# Standing_Desk_Controller_Schematic_v20_v.net
KiCad netlist of a schematic drawn in EAGLE
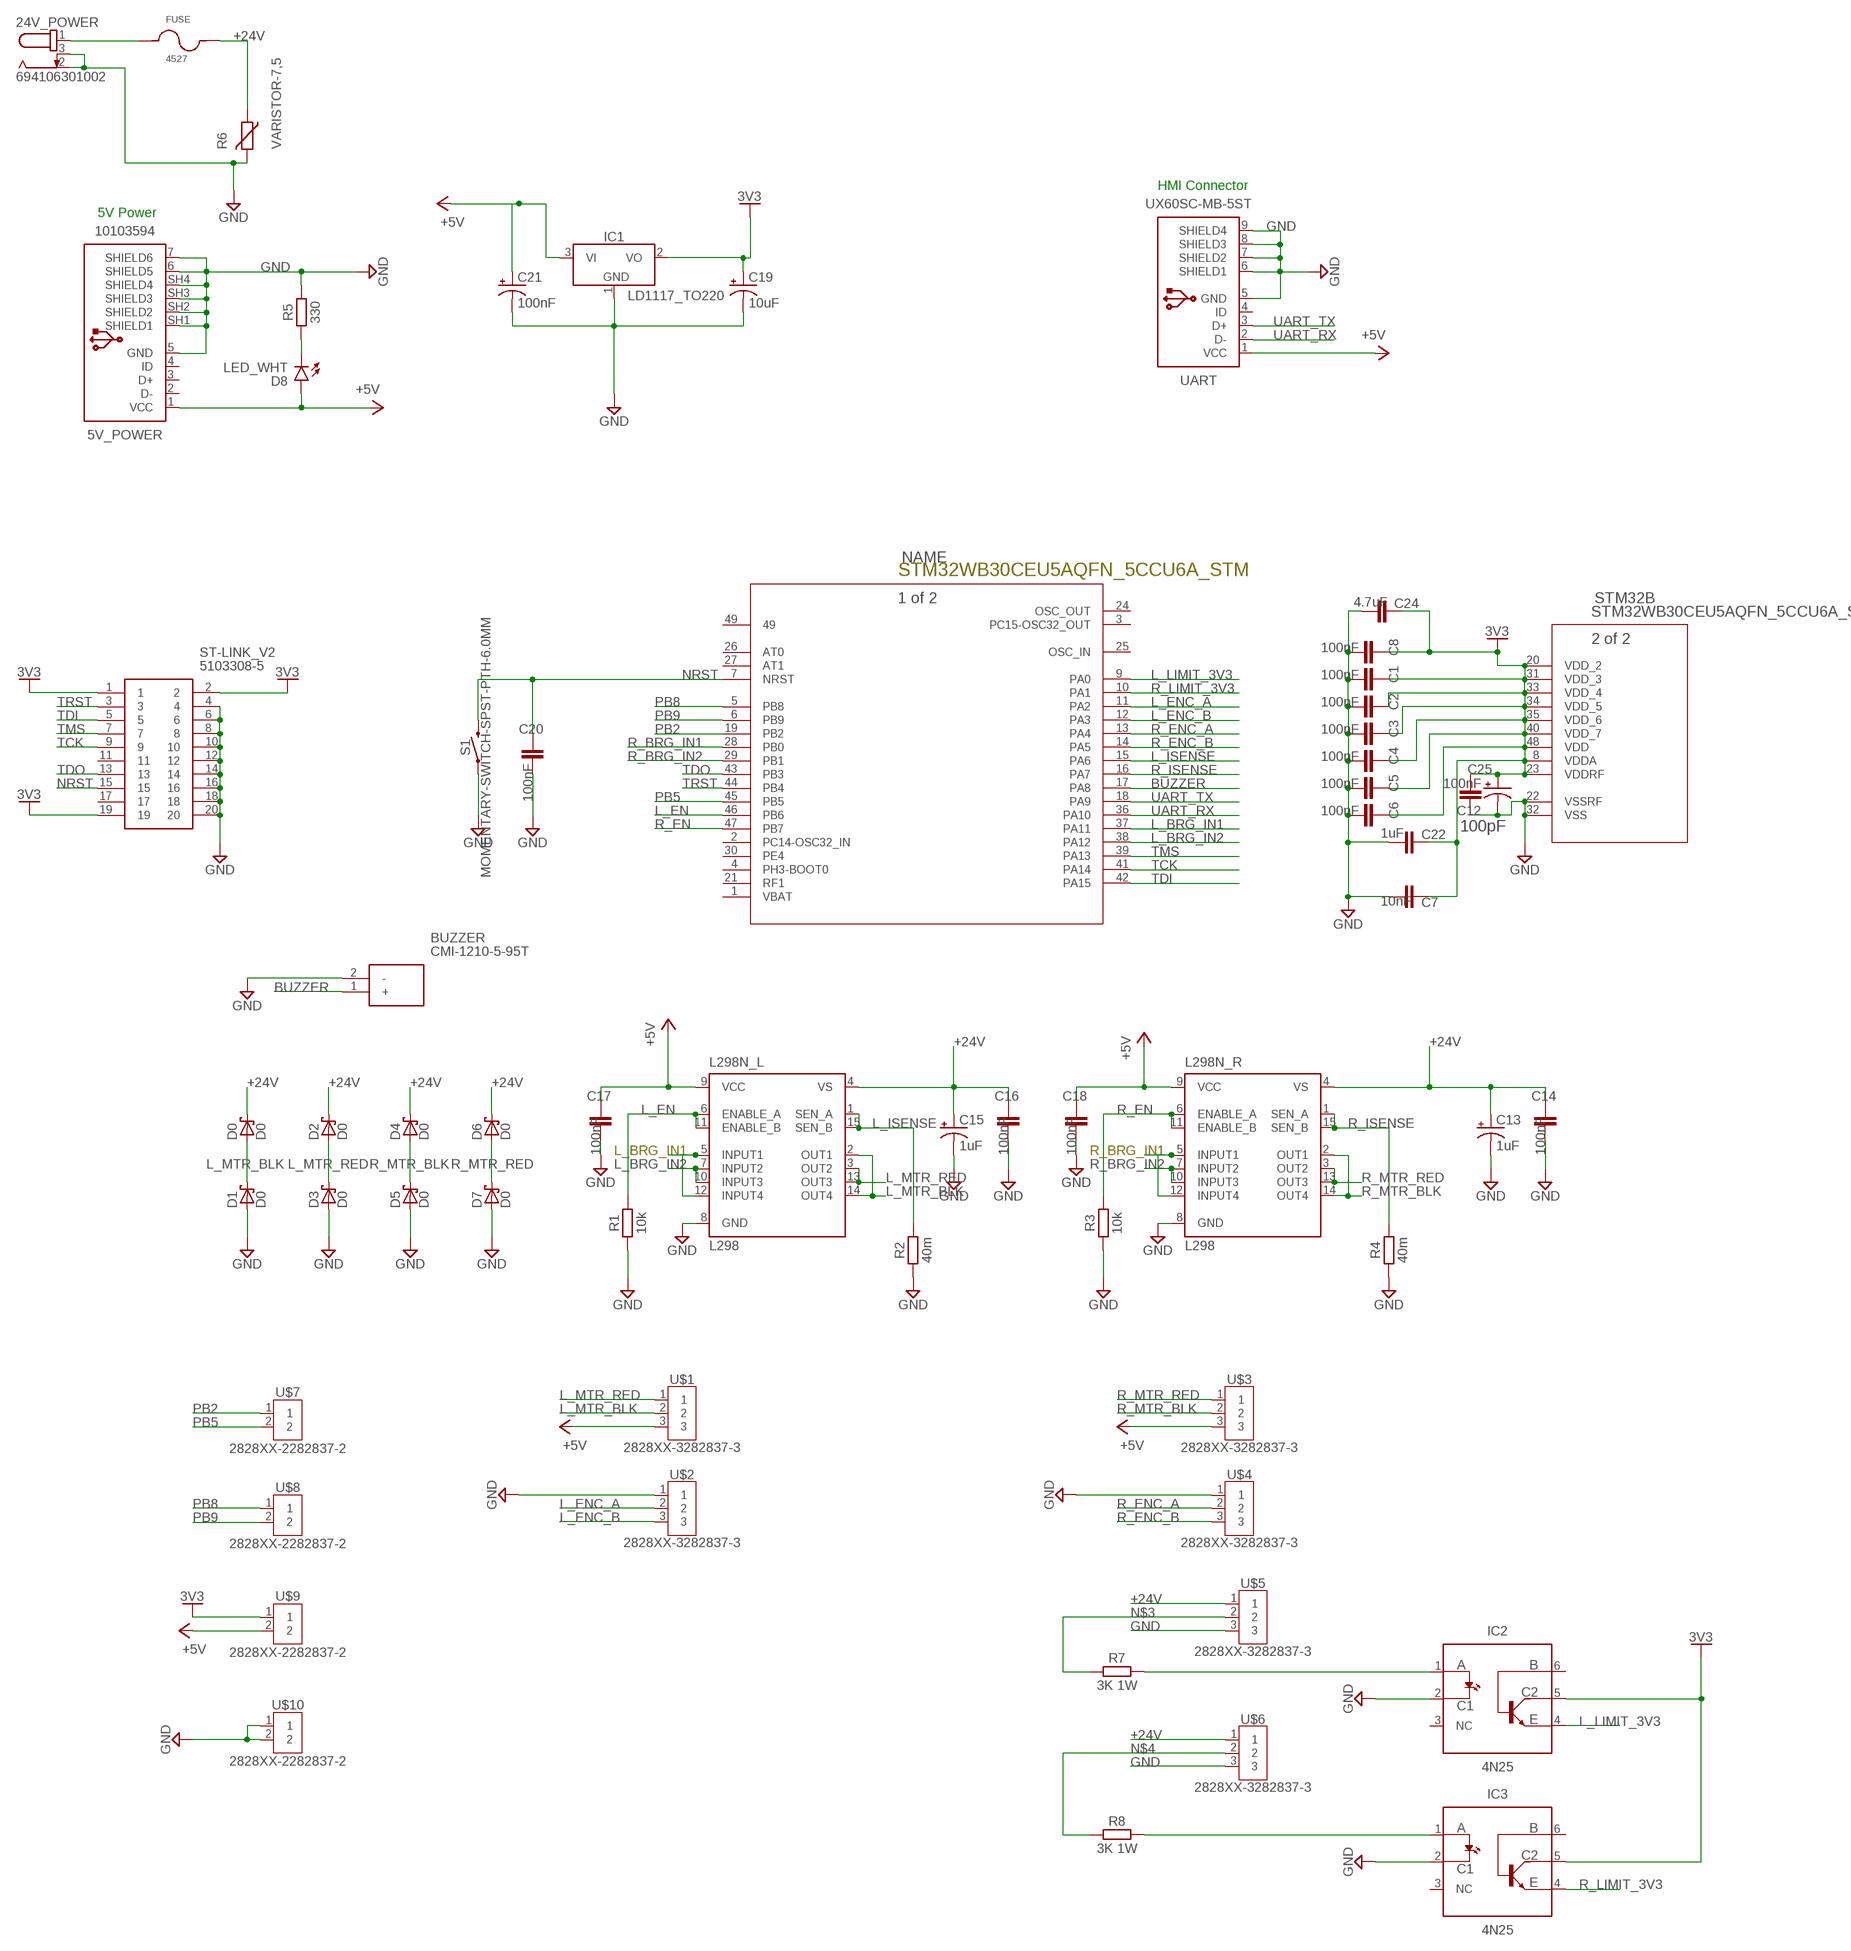
[diagram p0: schematic, sheet 1]

(export (version "E")
  (design (tool "Eeschema 10.0.6"))
  (components
    (comp (ref "5V_POWER")
      (value "10103594")
      (footprint "eagle-import:10103594")
      (fields (field (name "MANUFACTURER") "Amphenol ICC (FCI)") (field (name "MPN") "10103594-0001LF"))
      (libsource (lib "eagle-import") (part "10103594"))
    )
    (comp (ref "24V_POWER")
      (value "694106301002")
      (footprint "eagle-import:694106301002")
      (fields
        (field (name "DIGIKEY_PART_NUMBER") "732-5930-ND")
        (field (name "MANUFACTURER") "Wurth Electronics Inc.")
        (field (name "CREATED_BY") "PCBLayout.com")
      )
      (libsource (lib "eagle-import") (part "694106301002"))
    )
    (comp (ref "BUZZER")
      (value "CMI-1210-5-95T")
      (footprint "eagle-import:CMI1210595T")
      (fields (field (name "MOUSER_PART_NUMBER") "179-CMI-1210-5-95T"))
      (libsource (lib "eagle-import") (part "CMI-1210-5-95T"))
    )
    (comp (ref "C1")
      (value "100nF")
      (footprint "eagle-import:CAPC3216X135")
      (libsource (lib "eagle-import") (part "Capacitor_Bottom_Side_vf.a7xvLcyfRC6FgNyyCREhQg_CCHIP-1206(3216-METRIC)_"))
    )
    (comp (ref "C2")
      (value "100nF")
      (footprint "eagle-import:CAPC3216X135")
      (libsource (lib "eagle-import") (part "Capacitor_Bottom_Side_vf.a7xvLcyfRC6FgNyyCREhQg_CCHIP-1206(3216-METRIC)_"))
    )
    (comp (ref "C3")
      (value "100nF")
      (footprint "eagle-import:CAPC3216X135")
      (libsource (lib "eagle-import") (part "Capacitor_Bottom_Side_vf.a7xvLcyfRC6FgNyyCREhQg_CCHIP-1206(3216-METRIC)_"))
    )
    (comp (ref "C4")
      (value "100nF")
      (footprint "eagle-import:CAPC3216X135")
      (libsource (lib "eagle-import") (part "Capacitor_Bottom_Side_vf.a7xvLcyfRC6FgNyyCREhQg_CCHIP-1206(3216-METRIC)_"))
    )
    (comp (ref "C5")
      (value "100nF")
      (footprint "eagle-import:CAPC3216X135")
      (libsource (lib "eagle-import") (part "Capacitor_Bottom_Side_vf.a7xvLcyfRC6FgNyyCREhQg_CCHIP-1206(3216-METRIC)_"))
    )
    (comp (ref "C6")
      (value "100nF")
      (footprint "eagle-import:CAPC3216X135")
      (libsource (lib "eagle-import") (part "Capacitor_Bottom_Side_vf.a7xvLcyfRC6FgNyyCREhQg_CCHIP-1206(3216-METRIC)_"))
    )
    (comp (ref "C7")
      (value "10nF")
      (footprint "eagle-import:CAPRD550W60D1025H1250B")
      (libsource (lib "eagle-import") (part "CRADIAL-12.5MM-DIA_"))
    )
    (comp (ref "C8")
      (value "100nF")
      (footprint "eagle-import:CAPC3216X135")
      (libsource (lib "eagle-import") (part "Capacitor_Bottom_Side_vf.a7xvLcyfRC6FgNyyCREhQg_CCHIP-1206(3216-METRIC)_"))
    )
    (comp (ref "C12")
      (value "100nF")
      (footprint "eagle-import:CAPC3216X135")
      (libsource (lib "eagle-import") (part "Capacitor_Bottom_Side_vf.a7xvLcyfRC6FgNyyCREhQg_CCHIP-1206(3216-METRIC)_"))
    )
    (comp (ref "C13")
      (value "1uF")
      (footprint "eagle-import:E2,5-6")
      (libsource (lib "eagle-import") (part "CPOL-USE2.5-6"))
    )
    (comp (ref "C14")
      (value "100nF")
      (footprint "eagle-import:CAPC3216X135")
      (libsource (lib "eagle-import") (part "Capacitor_16290819_CCHIP-1206(3216-METRIC)_"))
    )
    (comp (ref "C15")
      (value "1uF")
      (footprint "eagle-import:E2,5-6")
      (libsource (lib "eagle-import") (part "CPOL-USE2.5-6"))
    )
    (comp (ref "C16")
      (value "100nF")
      (footprint "eagle-import:CAPC3216X135")
      (libsource (lib "eagle-import") (part "Capacitor_16290819_CCHIP-1206(3216-METRIC)_"))
    )
    (comp (ref "C17")
      (value "100nF")
      (footprint "eagle-import:CAPC3216X135")
      (libsource (lib "eagle-import") (part "Capacitor_16290819_CCHIP-1206(3216-METRIC)_"))
    )
    (comp (ref "C18")
      (value "100nF")
      (footprint "eagle-import:CAPC3216X135")
      (libsource (lib "eagle-import") (part "Capacitor_16290819_CCHIP-1206(3216-METRIC)_"))
    )
    (comp (ref "C19")
      (value "10uF")
      (footprint "eagle-import:E2,5-6")
      (libsource (lib "eagle-import") (part "CPOL-USE2.5-6"))
    )
    (comp (ref "C20")
      (value "100nF")
      (footprint "eagle-import:CAPC3216X135")
      (libsource (lib "eagle-import") (part "Capacitor_16290819_CCHIP-1206(3216-METRIC)_"))
    )
    (comp (ref "C21")
      (value "100nF")
      (footprint "eagle-import:E2,5-6")
      (libsource (lib "eagle-import") (part "CPOL-USE2.5-6"))
    )
    (comp (ref "C22")
      (value "1uF")
      (footprint "eagle-import:CAPRD550W60D1025H1250B")
      (libsource (lib "eagle-import") (part "CRADIAL-12.5MM-DIA_"))
    )
    (comp (ref "C24")
      (value "4.7uF")
      (footprint "eagle-import:CAPRD550W60D1025H1250B")
      (libsource (lib "eagle-import") (part "CRADIAL-12.5MM-DIA_"))
    )
    (comp (ref "C25")
      (value "100pF")
      (footprint "eagle-import:E2,5-6")
      (libsource (lib "eagle-import") (part "CPOL-USE2.5-6"))
    )
    (comp (ref "D0")
      (value "D0")
      (footprint "eagle-import:SOD106A-W")
      (libsource (lib "eagle-import") (part "SS14CT-ND"))
    )
    (comp (ref "D1")
      (value "D0")
      (footprint "eagle-import:SOD106A-W")
      (libsource (lib "eagle-import") (part "SS14CT-ND"))
    )
    (comp (ref "D2")
      (value "D0")
      (footprint "eagle-import:SOD106A-W")
      (libsource (lib "eagle-import") (part "SS14CT-ND"))
    )
    (comp (ref "D3")
      (value "D0")
      (footprint "eagle-import:SOD106A-W")
      (libsource (lib "eagle-import") (part "SS14CT-ND"))
    )
    (comp (ref "D4")
      (value "D0")
      (footprint "eagle-import:SOD106A-W")
      (libsource (lib "eagle-import") (part "SS14CT-ND"))
    )
    (comp (ref "D5")
      (value "D0")
      (footprint "eagle-import:SOD106A-W")
      (libsource (lib "eagle-import") (part "SS14CT-ND"))
    )
    (comp (ref "D6")
      (value "D0")
      (footprint "eagle-import:SOD106A-W")
      (libsource (lib "eagle-import") (part "SS14CT-ND"))
    )
    (comp (ref "D7")
      (value "D0")
      (footprint "eagle-import:SOD106A-W")
      (libsource (lib "eagle-import") (part "SS14CT-ND"))
    )
    (comp (ref "D8")
      (value "LED_WHT")
      (footprint "eagle-import:LEDC3216X75N_FLAT-B")
      (libsource (lib "eagle-import") (part "CHIP-FLAT-B_1206"))
    )
    (comp (ref "FUSE")
      (value "4527")
      (footprint "eagle-import:4527")
      (fields
        (field (name "MANUFACTURER") "Keystone Electronics")
        (field (name "CREATED_BY") "PCBLayout.com")
      )
      (libsource (lib "eagle-import") (part "4527"))
    )
    (comp (ref "IC1")
      (value "LD1117_TO220")
      (footprint "eagle-import:TO220V")
      (fields (field (name "MANUFACTURER") "STMicroelectronics") (field (name "MPN") "Generic"))
      (libsource (lib "eagle-import") (part "LD1117_TO220"))
    )
    (comp (ref "IC2")
      (value "4N25")
      (footprint "eagle-import:DIP762W60P254L712H480Q6B")
      (fields (field (name "MANUFACTURER") "Vishay"))
      (libsource (lib "eagle-import") (part "4N25"))
    )
    (comp (ref "IC3")
      (value "4N25")
      (footprint "eagle-import:DIP762W60P254L712H480Q6B")
      (fields (field (name "MANUFACTURER") "Vishay"))
      (libsource (lib "eagle-import") (part "4N25"))
    )
    (comp (ref "L298N_L")
      (value "L298")
      (footprint "eagle-import:MULTIWATT-15")
      (fields (field (name "MPN") "L298N"))
      (libsource (lib "eagle-import") (part "L298"))
    )
    (comp (ref "L298N_R")
      (value "L298")
      (footprint "eagle-import:MULTIWATT-15")
      (fields (field (name "MPN") "L298N"))
      (libsource (lib "eagle-import") (part "L298"))
    )
    (comp (ref "R1")
      (value "10k")
      (footprint "eagle-import:RESC3216X70")
      (libsource (lib "eagle-import") (part "RCHIP-1206(3216-METRIC)_"))
    )
    (comp (ref "R2")
      (value "40m")
      (footprint "eagle-import:RESC3216X70")
      (libsource (lib "eagle-import") (part "RCHIP-1206(3216-METRIC)_"))
    )
    (comp (ref "R3")
      (value "10k")
      (footprint "eagle-import:RESC3216X70")
      (libsource (lib "eagle-import") (part "RCHIP-1206(3216-METRIC)_"))
    )
    (comp (ref "R4")
      (value "40m")
      (footprint "eagle-import:RESC3216X70")
      (libsource (lib "eagle-import") (part "RCHIP-1206(3216-METRIC)_"))
    )
    (comp (ref "R5")
      (value "330")
      (footprint "eagle-import:RESC3216X70")
      (libsource (lib "eagle-import") (part "RCHIP-1206(3216-METRIC)_"))
    )
    (comp (ref "R6")
      (value "VARISTOR-7,5")
      (footprint "eagle-import:R-7,5")
      (libsource (lib "eagle-import") (part "VARISTOR-7,5"))
    )
    (comp (ref "R7")
      (value "3K 1W")
      (footprint "eagle-import:RESAD724W46L381D178B")
      (libsource (lib "eagle-import") (part "RAXIAL-7.2MM-PITCH_"))
    )
    (comp (ref "R8")
      (value "3K 1W")
      (footprint "eagle-import:RESAD724W46L381D178B")
      (libsource (lib "eagle-import") (part "RAXIAL-7.2MM-PITCH_"))
    )
    (comp (ref "S1")
      (value "MOMENTARY-SWITCH-SPST-PTH-6.0MM")
      (footprint "eagle-import:TACTILE_SWITCH_PTH_6.0MM")
      (libsource (lib "eagle-import") (part "MOMENTARY-SWITCH-SPST-PTH-6.0MM"))
    )
    (comp (ref "ST-LINK_V2")
      (value "5103308-5")
      (footprint "eagle-import:SHDR20W66P254_2X10_3289X914X98")
      (fields (field (name "MOUSER_PART_NUMBER") "571-5103308-5"))
      (libsource (lib "eagle-import") (part "5103308-5"))
    )
    (comp (ref "STM32")
      (value "STM32WB30CEU5AQFN_5CCU6A_STM")
      (footprint "eagle-import:QFN_5CCU6A_STM")
      (fields
        (field (name "MANUFACTURER_PART_NUMBER") "STM32WB30CEU5A")
        (field (name "COPYRIGHT") "Copyright (C) 2022 Ultra Librarian. All rights reserved.")
      )
      (libsource (lib "eagle-import") (part "STM32WB30CEU5AQFN_5CCU6A_STM"))
    )
    (comp (ref "U$1")
      (value "2828XX-3282837-3")
      (footprint "eagle-import:TERMBLK_508-3N")
      (fields (field (name "MANUFACTURER") "TE Connectivity") (field (name "MPN") "282837-3"))
      (libsource (lib "eagle-import") (part "2828XX-3282837-3"))
    )
    (comp (ref "U$2")
      (value "2828XX-3282837-3")
      (footprint "eagle-import:TERMBLK_508-3N")
      (fields (field (name "MANUFACTURER") "TE Connectivity") (field (name "MPN") "282837-3"))
      (libsource (lib "eagle-import") (part "2828XX-3282837-3"))
    )
    (comp (ref "U$3")
      (value "2828XX-3282837-3")
      (footprint "eagle-import:TERMBLK_508-3N")
      (fields (field (name "MANUFACTURER") "TE Connectivity") (field (name "MPN") "282837-3"))
      (libsource (lib "eagle-import") (part "2828XX-3282837-3"))
    )
    (comp (ref "U$4")
      (value "2828XX-3282837-3")
      (footprint "eagle-import:TERMBLK_508-3N")
      (fields (field (name "MANUFACTURER") "TE Connectivity") (field (name "MPN") "282837-3"))
      (libsource (lib "eagle-import") (part "2828XX-3282837-3"))
    )
    (comp (ref "U$5")
      (value "2828XX-3282837-3")
      (footprint "eagle-import:TERMBLK_508-3N")
      (fields (field (name "MANUFACTURER") "TE Connectivity") (field (name "MPN") "282837-3"))
      (libsource (lib "eagle-import") (part "2828XX-3282837-3"))
    )
    (comp (ref "U$6")
      (value "2828XX-3282837-3")
      (footprint "eagle-import:TERMBLK_508-3N")
      (fields (field (name "MANUFACTURER") "TE Connectivity") (field (name "MPN") "282837-3"))
      (libsource (lib "eagle-import") (part "2828XX-3282837-3"))
    )
    (comp (ref "U$7")
      (value "2828XX-2282837-2")
      (footprint "eagle-import:TERMBLK_508-2N")
      (fields (field (name "MANUFACTURER") "TE Connectivity") (field (name "MPN") "282837-2"))
      (libsource (lib "eagle-import") (part "2828XX-2282837-2"))
    )
    (comp (ref "U$8")
      (value "2828XX-2282837-2")
      (footprint "eagle-import:TERMBLK_508-2N")
      (fields (field (name "MANUFACTURER") "TE Connectivity") (field (name "MPN") "282837-2"))
      (libsource (lib "eagle-import") (part "2828XX-2282837-2"))
    )
    (comp (ref "U$9")
      (value "2828XX-2282837-2")
      (footprint "eagle-import:TERMBLK_508-2N")
      (fields (field (name "MANUFACTURER") "TE Connectivity") (field (name "MPN") "282837-2"))
      (libsource (lib "eagle-import") (part "2828XX-2282837-2"))
    )
    (comp (ref "U$10")
      (value "2828XX-2282837-2")
      (footprint "eagle-import:TERMBLK_508-2N")
      (fields (field (name "MANUFACTURER") "TE Connectivity") (field (name "MPN") "282837-2"))
      (libsource (lib "eagle-import") (part "2828XX-2282837-2"))
    )
    (comp (ref "UART")
      (value "UX60SC-MB-5ST")
      (footprint "eagle-import:UX60SC-MB-5ST")
      (fields
        (field (name "MANUFACTURER") "Hirose Electric Co. Ltd")
        (field (name "MPN") "UX60SC-MB-5ST(80)")
      )
      (libsource (lib "eagle-import") (part "UX60SC-MB-5ST"))
    )
  )
  (nets
    (net (code "1") (name "+5V") (class "Default")
      (node (ref "5V_POWER") (pin "1") (pinfunction "VCC_1") (pintype "power_in"))
      (node (ref "C17") (pin "1") (pinfunction "1_1") (pintype "passive"))
      (node (ref "C18") (pin "1") (pinfunction "1_1") (pintype "passive"))
      (node (ref "C21") (pin "+") (pinfunction "+_+") (pintype "passive"))
      (node (ref "D8") (pin "A") (pinfunction "A_A") (pintype "passive"))
      (node (ref "IC1") (pin "3") (pinfunction "VI_3") (pintype "input"))
      (node (ref "L298N_L") (pin "9") (pinfunction "VCC_9") (pintype "power_in"))
      (node (ref "L298N_R") (pin "9") (pinfunction "VCC_9") (pintype "power_in"))
      (node (ref "U$1") (pin "3") (pinfunction "3_3") (pintype "bidirectional"))
      (node (ref "U$3") (pin "3") (pinfunction "3_3") (pintype "bidirectional"))
      (node (ref "U$9") (pin "2") (pinfunction "2_2") (pintype "bidirectional"))
      (node (ref "UART") (pin "1") (pinfunction "VCC_1") (pintype "power_in"))
    )
    (net (code "2") (name "/+24V") (class "Default")
      (node (ref "C13") (pin "+") (pinfunction "+_+") (pintype "passive"))
      (node (ref "C14") (pin "1") (pinfunction "1_1") (pintype "passive"))
      (node (ref "C15") (pin "+") (pinfunction "+_+") (pintype "passive"))
      (node (ref "C16") (pin "1") (pinfunction "1_1") (pintype "passive"))
      (node (ref "D0") (pin "C") (pinfunction "C_C") (pintype "passive"))
      (node (ref "D2") (pin "C") (pinfunction "C_C") (pintype "passive"))
      (node (ref "D4") (pin "C") (pinfunction "C_C") (pintype "passive"))
      (node (ref "D6") (pin "C") (pinfunction "C_C") (pintype "passive"))
      (node (ref "FUSE") (pin "2") (pinfunction "2_2") (pintype "passive"))
      (node (ref "L298N_L") (pin "4") (pinfunction "VS_4") (pintype "power_in"))
      (node (ref "L298N_R") (pin "4") (pinfunction "VS_4") (pintype "power_in"))
      (node (ref "R6") (pin "1") (pinfunction "1_1") (pintype "passive"))
      (node (ref "U$5") (pin "1") (pinfunction "1_1") (pintype "bidirectional"))
      (node (ref "U$6") (pin "1") (pinfunction "1_1") (pintype "bidirectional"))
    )
    (net (code "3") (name "/BUZZER") (class "Default")
      (node (ref "BUZZER") (pin "1") (pinfunction "+_1") (pintype "bidirectional"))
      (node (ref "STM32") (pin "17") (pinfunction "PA8_17") (pintype "bidirectional"))
    )
    (net (code "4") (name "/L_BRG_IN1") (class "Default")
      (node (ref "L298N_L") (pin "12") (pinfunction "INPUT4_12") (pintype "input"))
      (node (ref "L298N_L") (pin "5") (pinfunction "INPUT1_5") (pintype "input"))
      (node (ref "STM32") (pin "37") (pinfunction "PA11_37") (pintype "bidirectional"))
    )
    (net (code "5") (name "/L_BRG_IN2") (class "Default")
      (node (ref "L298N_L") (pin "10") (pinfunction "INPUT3_10") (pintype "input"))
      (node (ref "L298N_L") (pin "7") (pinfunction "INPUT2_7") (pintype "input"))
      (node (ref "STM32") (pin "38") (pinfunction "PA12_38") (pintype "bidirectional"))
    )
    (net (code "6") (name "/L_EN") (class "Default")
      (node (ref "L298N_L") (pin "11") (pinfunction "ENABLE_B_11") (pintype "input"))
      (node (ref "L298N_L") (pin "6") (pinfunction "ENABLE_A_6") (pintype "input"))
      (node (ref "R1") (pin "2") (pinfunction "2_2") (pintype "passive"))
      (node (ref "STM32") (pin "46") (pinfunction "PB6_46") (pintype "bidirectional"))
    )
    (net (code "7") (name "/L_ENC_A") (class "Default")
      (node (ref "STM32") (pin "11") (pinfunction "PA2_11") (pintype "bidirectional"))
      (node (ref "U$2") (pin "2") (pinfunction "2_2") (pintype "bidirectional"))
    )
    (net (code "8") (name "/L_ENC_B") (class "Default")
      (node (ref "STM32") (pin "12") (pinfunction "PA3_12") (pintype "bidirectional"))
      (node (ref "U$2") (pin "3") (pinfunction "3_3") (pintype "bidirectional"))
    )
    (net (code "9") (name "/L_ISENSE") (class "Default")
      (node (ref "L298N_L") (pin "1") (pinfunction "SEN_A_1") (pintype "input"))
      (node (ref "L298N_L") (pin "15") (pinfunction "SEN_B_15") (pintype "input"))
      (node (ref "R2") (pin "2") (pinfunction "2_2") (pintype "passive"))
      (node (ref "STM32") (pin "15") (pinfunction "PA6_15") (pintype "bidirectional"))
    )
    (net (code "10") (name "/L_LIMIT_3V3") (class "Default")
      (node (ref "IC2") (pin "4") (pinfunction "E_4") (pintype "passive"))
      (node (ref "STM32") (pin "9") (pinfunction "PA0_9") (pintype "bidirectional"))
    )
    (net (code "11") (name "/L_MTR_BLK") (class "Default")
      (node (ref "D0") (pin "A") (pinfunction "A_A") (pintype "passive"))
      (node (ref "D1") (pin "C") (pinfunction "C_C") (pintype "passive"))
      (node (ref "L298N_L") (pin "14") (pinfunction "OUT4_14") (pintype "output"))
      (node (ref "L298N_L") (pin "2") (pinfunction "OUT1_2") (pintype "output"))
      (node (ref "U$1") (pin "2") (pinfunction "2_2") (pintype "bidirectional"))
    )
    (net (code "12") (name "/L_MTR_RED") (class "Default")
      (node (ref "D2") (pin "A") (pinfunction "A_A") (pintype "passive"))
      (node (ref "D3") (pin "C") (pinfunction "C_C") (pintype "passive"))
      (node (ref "L298N_L") (pin "13") (pinfunction "OUT3_13") (pintype "output"))
      (node (ref "L298N_L") (pin "3") (pinfunction "OUT2_3") (pintype "output"))
      (node (ref "U$1") (pin "1") (pinfunction "1_1") (pintype "bidirectional"))
    )
    (net (code "13") (name "/N$3") (class "Default")
      (node (ref "R7") (pin "1") (pinfunction "1_1") (pintype "passive"))
      (node (ref "U$5") (pin "2") (pinfunction "2_2") (pintype "bidirectional"))
    )
    (net (code "14") (name "/N$4") (class "Default")
      (node (ref "R8") (pin "1") (pinfunction "1_1") (pintype "passive"))
      (node (ref "U$6") (pin "2") (pinfunction "2_2") (pintype "bidirectional"))
    )
    (net (code "15") (name "/NRST") (class "Default")
      (node (ref "C20") (pin "1") (pinfunction "1_1") (pintype "passive"))
      (node (ref "S1") (pin "3") (pinfunction "2_3") (pintype "passive"))
      (node (ref "ST-LINK_V2") (pin "15") (pinfunction "15_15") (pintype "bidirectional"))
      (node (ref "STM32") (pin "7") (pinfunction "NRST_7") (pintype "passive"))
    )
    (net (code "16") (name "/PB2") (class "Default")
      (node (ref "STM32") (pin "19") (pinfunction "PB2_19") (pintype "bidirectional"))
      (node (ref "U$7") (pin "1") (pinfunction "1_1") (pintype "bidirectional"))
    )
    (net (code "17") (name "/PB5") (class "Default")
      (node (ref "STM32") (pin "45") (pinfunction "PB5_45") (pintype "bidirectional"))
      (node (ref "U$7") (pin "2") (pinfunction "2_2") (pintype "bidirectional"))
    )
    (net (code "18") (name "/PB8") (class "Default")
      (node (ref "STM32") (pin "5") (pinfunction "PB8_5") (pintype "bidirectional"))
      (node (ref "U$8") (pin "1") (pinfunction "1_1") (pintype "bidirectional"))
    )
    (net (code "19") (name "/PB9") (class "Default")
      (node (ref "STM32") (pin "6") (pinfunction "PB9_6") (pintype "bidirectional"))
      (node (ref "U$8") (pin "2") (pinfunction "2_2") (pintype "bidirectional"))
    )
    (net (code "20") (name "/R_BRG_IN1") (class "Default")
      (node (ref "L298N_R") (pin "12") (pinfunction "INPUT4_12") (pintype "input"))
      (node (ref "L298N_R") (pin "5") (pinfunction "INPUT1_5") (pintype "input"))
      (node (ref "STM32") (pin "28") (pinfunction "PB0_28") (pintype "bidirectional"))
    )
    (net (code "21") (name "/R_BRG_IN2") (class "Default")
      (node (ref "L298N_R") (pin "10") (pinfunction "INPUT3_10") (pintype "input"))
      (node (ref "L298N_R") (pin "7") (pinfunction "INPUT2_7") (pintype "input"))
      (node (ref "STM32") (pin "29") (pinfunction "PB1_29") (pintype "bidirectional"))
    )
    (net (code "22") (name "/R_EN") (class "Default")
      (node (ref "L298N_R") (pin "11") (pinfunction "ENABLE_B_11") (pintype "input"))
      (node (ref "L298N_R") (pin "6") (pinfunction "ENABLE_A_6") (pintype "input"))
      (node (ref "R3") (pin "2") (pinfunction "2_2") (pintype "passive"))
      (node (ref "STM32") (pin "47") (pinfunction "PB7_47") (pintype "bidirectional"))
    )
    (net (code "23") (name "/R_ENC_A") (class "Default")
      (node (ref "STM32") (pin "13") (pinfunction "PA4_13") (pintype "bidirectional"))
      (node (ref "U$4") (pin "2") (pinfunction "2_2") (pintype "bidirectional"))
    )
    (net (code "24") (name "/R_ENC_B") (class "Default")
      (node (ref "STM32") (pin "14") (pinfunction "PA5_14") (pintype "bidirectional"))
      (node (ref "U$4") (pin "3") (pinfunction "3_3") (pintype "bidirectional"))
    )
    (net (code "25") (name "/R_ISENSE") (class "Default")
      (node (ref "L298N_R") (pin "1") (pinfunction "SEN_A_1") (pintype "input"))
      (node (ref "L298N_R") (pin "15") (pinfunction "SEN_B_15") (pintype "input"))
      (node (ref "R4") (pin "2") (pinfunction "2_2") (pintype "passive"))
      (node (ref "STM32") (pin "16") (pinfunction "PA7_16") (pintype "bidirectional"))
    )
    (net (code "26") (name "/R_LIMIT_3V3") (class "Default")
      (node (ref "IC3") (pin "4") (pinfunction "E_4") (pintype "passive"))
      (node (ref "STM32") (pin "10") (pinfunction "PA1_10") (pintype "bidirectional"))
    )
    (net (code "27") (name "/R_MTR_BLK") (class "Default")
      (node (ref "D4") (pin "A") (pinfunction "A_A") (pintype "passive"))
      (node (ref "D5") (pin "C") (pinfunction "C_C") (pintype "passive"))
      (node (ref "L298N_R") (pin "14") (pinfunction "OUT4_14") (pintype "output"))
      (node (ref "L298N_R") (pin "2") (pinfunction "OUT1_2") (pintype "output"))
      (node (ref "U$3") (pin "2") (pinfunction "2_2") (pintype "bidirectional"))
    )
    (net (code "28") (name "/R_MTR_RED") (class "Default")
      (node (ref "D6") (pin "A") (pinfunction "A_A") (pintype "passive"))
      (node (ref "D7") (pin "C") (pinfunction "C_C") (pintype "passive"))
      (node (ref "L298N_R") (pin "13") (pinfunction "OUT3_13") (pintype "output"))
      (node (ref "L298N_R") (pin "3") (pinfunction "OUT2_3") (pintype "output"))
      (node (ref "U$3") (pin "1") (pinfunction "1_1") (pintype "bidirectional"))
    )
    (net (code "29") (name "/TCK") (class "Default")
      (node (ref "ST-LINK_V2") (pin "9") (pinfunction "9_9") (pintype "bidirectional"))
      (node (ref "STM32") (pin "41") (pinfunction "PA14_41") (pintype "bidirectional"))
    )
    (net (code "30") (name "/TDI") (class "Default")
      (node (ref "ST-LINK_V2") (pin "5") (pinfunction "5_5") (pintype "bidirectional"))
      (node (ref "STM32") (pin "42") (pinfunction "PA15_42") (pintype "bidirectional"))
    )
    (net (code "31") (name "/TDO") (class "Default")
      (node (ref "ST-LINK_V2") (pin "13") (pinfunction "13_13") (pintype "bidirectional"))
      (node (ref "STM32") (pin "43") (pinfunction "PB3_43") (pintype "bidirectional"))
    )
    (net (code "32") (name "/TMS") (class "Default")
      (node (ref "ST-LINK_V2") (pin "7") (pinfunction "7_7") (pintype "bidirectional"))
      (node (ref "STM32") (pin "39") (pinfunction "PA13_39") (pintype "bidirectional"))
    )
    (net (code "33") (name "/TRST") (class "Default")
      (node (ref "ST-LINK_V2") (pin "3") (pinfunction "3_3") (pintype "bidirectional"))
      (node (ref "STM32") (pin "44") (pinfunction "PB4_44") (pintype "bidirectional"))
    )
    (net (code "34") (name "/UART_RX") (class "Default")
      (node (ref "STM32") (pin "36") (pinfunction "PA10_36") (pintype "bidirectional"))
      (node (ref "UART") (pin "2") (pinfunction "D-_2") (pintype "bidirectional"))
    )
    (net (code "35") (name "/UART_TX") (class "Default")
      (node (ref "STM32") (pin "18") (pinfunction "PA9_18") (pintype "bidirectional"))
      (node (ref "UART") (pin "3") (pinfunction "D+_3") (pintype "bidirectional"))
    )
    (net (code "36") (name "3V3") (class "Default")
      (node (ref "C1") (pin "1") (pinfunction "1_1") (pintype "passive"))
      (node (ref "C12") (pin "1") (pinfunction "1_1") (pintype "passive"))
      (node (ref "C19") (pin "+") (pinfunction "+_+") (pintype "passive"))
      (node (ref "C2") (pin "1") (pinfunction "1_1") (pintype "passive"))
      (node (ref "C22") (pin "1") (pinfunction "1_1") (pintype "passive"))
      (node (ref "C24") (pin "1") (pinfunction "1_1") (pintype "passive"))
      (node (ref "C25") (pin "+") (pinfunction "+_+") (pintype "passive"))
      (node (ref "C3") (pin "1") (pinfunction "1_1") (pintype "passive"))
      (node (ref "C4") (pin "1") (pinfunction "1_1") (pintype "passive"))
      (node (ref "C5") (pin "1") (pinfunction "1_1") (pintype "passive"))
      (node (ref "C6") (pin "1") (pinfunction "1_1") (pintype "passive"))
      (node (ref "C7") (pin "1") (pinfunction "1_1") (pintype "passive"))
      (node (ref "C8") (pin "1") (pinfunction "1_1") (pintype "passive"))
      (node (ref "IC1") (pin "2") (pinfunction "VO_2") (pintype "output"))
      (node (ref "IC2") (pin "5") (pinfunction "C2_5") (pintype "passive"))
      (node (ref "IC3") (pin "5") (pinfunction "C2_5") (pintype "passive"))
      (node (ref "ST-LINK_V2") (pin "1") (pinfunction "1_1") (pintype "bidirectional"))
      (node (ref "ST-LINK_V2") (pin "19") (pinfunction "19_19") (pintype "bidirectional"))
      (node (ref "ST-LINK_V2") (pin "2") (pinfunction "2_2") (pintype "bidirectional"))
      (node (ref "STM32") (pin "20") (pinfunction "VDD_2_20") (pintype "power_in"))
      (node (ref "STM32") (pin "23") (pinfunction "VDDRF_23") (pintype "power_in"))
      (node (ref "STM32") (pin "31") (pinfunction "VDD_3_31") (pintype "power_in"))
      (node (ref "STM32") (pin "33") (pinfunction "VDD_4_33") (pintype "power_in"))
      (node (ref "STM32") (pin "34") (pinfunction "VDD_5_34") (pintype "power_in"))
      (node (ref "STM32") (pin "35") (pinfunction "VDD_6_35") (pintype "power_in"))
      (node (ref "STM32") (pin "40") (pinfunction "VDD_7_40") (pintype "power_in"))
      (node (ref "STM32") (pin "48") (pinfunction "VDD_48") (pintype "power_in"))
      (node (ref "STM32") (pin "8") (pinfunction "VDDA_8") (pintype "power_in"))
      (node (ref "U$9") (pin "1") (pinfunction "1_1") (pintype "bidirectional"))
    )
    (net (code "37") (name "GND") (class "Default")
      (node (ref "24V_POWER") (pin "2") (pinfunction "2_2") (pintype "passive"))
      (node (ref "24V_POWER") (pin "3") (pinfunction "3_3") (pintype "passive"))
      (node (ref "5V_POWER") (pin "5") (pinfunction "GND_5") (pintype "power_in"))
      (node (ref "5V_POWER") (pin "6") (pinfunction "SHIELD5_6") (pintype "power_in"))
      (node (ref "5V_POWER") (pin "7") (pinfunction "SHIELD6_7") (pintype "power_in"))
      (node (ref "5V_POWER") (pin "SH1") (pinfunction "SHIELD1_SH1") (pintype "power_in"))
      (node (ref "5V_POWER") (pin "SH2") (pinfunction "SHIELD2_SH2") (pintype "power_in"))
      (node (ref "5V_POWER") (pin "SH3") (pinfunction "SHIELD3_SH3") (pintype "power_in"))
      (node (ref "5V_POWER") (pin "SH4") (pinfunction "SHIELD4_SH4") (pintype "power_in"))
      (node (ref "BUZZER") (pin "2") (pinfunction "-_2") (pintype "bidirectional"))
      (node (ref "C1") (pin "2") (pinfunction "2_2") (pintype "passive"))
      (node (ref "C12") (pin "2") (pinfunction "2_2") (pintype "passive"))
      (node (ref "C13") (pin "-") (pinfunction "-_-") (pintype "passive"))
      (node (ref "C14") (pin "2") (pinfunction "2_2") (pintype "passive"))
      (node (ref "C15") (pin "-") (pinfunction "-_-") (pintype "passive"))
      (node (ref "C16") (pin "2") (pinfunction "2_2") (pintype "passive"))
      (node (ref "C17") (pin "2") (pinfunction "2_2") (pintype "passive"))
      (node (ref "C18") (pin "2") (pinfunction "2_2") (pintype "passive"))
      (node (ref "C19") (pin "-") (pinfunction "-_-") (pintype "passive"))
      (node (ref "C2") (pin "2") (pinfunction "2_2") (pintype "passive"))
      (node (ref "C20") (pin "2") (pinfunction "2_2") (pintype "passive"))
      (node (ref "C21") (pin "-") (pinfunction "-_-") (pintype "passive"))
      (node (ref "C22") (pin "2") (pinfunction "2_2") (pintype "passive"))
      (node (ref "C24") (pin "2") (pinfunction "2_2") (pintype "passive"))
      (node (ref "C25") (pin "-") (pinfunction "-_-") (pintype "passive"))
      (node (ref "C3") (pin "2") (pinfunction "2_2") (pintype "passive"))
      (node (ref "C4") (pin "2") (pinfunction "2_2") (pintype "passive"))
      (node (ref "C5") (pin "2") (pinfunction "2_2") (pintype "passive"))
      (node (ref "C6") (pin "2") (pinfunction "2_2") (pintype "passive"))
      (node (ref "C7") (pin "2") (pinfunction "2_2") (pintype "passive"))
      (node (ref "C8") (pin "2") (pinfunction "2_2") (pintype "passive"))
      (node (ref "D1") (pin "A") (pinfunction "A_A") (pintype "passive"))
      (node (ref "D3") (pin "A") (pinfunction "A_A") (pintype "passive"))
      (node (ref "D5") (pin "A") (pinfunction "A_A") (pintype "passive"))
      (node (ref "D7") (pin "A") (pinfunction "A_A") (pintype "passive"))
      (node (ref "IC1") (pin "1") (pinfunction "GND_1") (pintype "passive"))
      (node (ref "IC2") (pin "2") (pinfunction "C1_2") (pintype "passive"))
      (node (ref "IC3") (pin "2") (pinfunction "C1_2") (pintype "passive"))
      (node (ref "L298N_L") (pin "8") (pinfunction "GND_8") (pintype "power_in"))
      (node (ref "L298N_R") (pin "8") (pinfunction "GND_8") (pintype "power_in"))
      (node (ref "R1") (pin "1") (pinfunction "1_1") (pintype "passive"))
      (node (ref "R2") (pin "1") (pinfunction "1_1") (pintype "passive"))
      (node (ref "R3") (pin "1") (pinfunction "1_1") (pintype "passive"))
      (node (ref "R4") (pin "1") (pinfunction "1_1") (pintype "passive"))
      (node (ref "R5") (pin "2") (pinfunction "2_2") (pintype "passive"))
      (node (ref "R6") (pin "2") (pinfunction "2_2") (pintype "passive"))
      (node (ref "S1") (pin "1") (pinfunction "1_1") (pintype "passive"))
      (node (ref "ST-LINK_V2") (pin "10") (pinfunction "10_10") (pintype "bidirectional"))
      (node (ref "ST-LINK_V2") (pin "12") (pinfunction "12_12") (pintype "bidirectional"))
      (node (ref "ST-LINK_V2") (pin "14") (pinfunction "14_14") (pintype "bidirectional"))
      (node (ref "ST-LINK_V2") (pin "16") (pinfunction "16_16") (pintype "bidirectional"))
      (node (ref "ST-LINK_V2") (pin "18") (pinfunction "18_18") (pintype "bidirectional"))
      (node (ref "ST-LINK_V2") (pin "20") (pinfunction "20_20") (pintype "bidirectional"))
      (node (ref "ST-LINK_V2") (pin "4") (pinfunction "4_4") (pintype "bidirectional"))
      (node (ref "ST-LINK_V2") (pin "6") (pinfunction "6_6") (pintype "bidirectional"))
      (node (ref "ST-LINK_V2") (pin "8") (pinfunction "8_8") (pintype "bidirectional"))
      (node (ref "STM32") (pin "22") (pinfunction "VSSRF_22") (pintype "passive"))
      (node (ref "STM32") (pin "32") (pinfunction "VSS_32") (pintype "passive"))
      (node (ref "U$10") (pin "1") (pinfunction "1_1") (pintype "bidirectional"))
      (node (ref "U$10") (pin "2") (pinfunction "2_2") (pintype "bidirectional"))
      (node (ref "U$2") (pin "1") (pinfunction "1_1") (pintype "bidirectional"))
      (node (ref "U$4") (pin "1") (pinfunction "1_1") (pintype "bidirectional"))
      (node (ref "U$5") (pin "3") (pinfunction "3_3") (pintype "bidirectional"))
      (node (ref "U$6") (pin "3") (pinfunction "3_3") (pintype "bidirectional"))
      (node (ref "UART") (pin "5") (pinfunction "GND_5") (pintype "power_in"))
      (node (ref "UART") (pin "6") (pinfunction "SHIELD1_6") (pintype "power_in"))
      (node (ref "UART") (pin "7") (pinfunction "SHIELD2_7") (pintype "power_in"))
      (node (ref "UART") (pin "8") (pinfunction "SHIELD3_8") (pintype "power_in"))
      (node (ref "UART") (pin "9") (pinfunction "SHIELD4_9") (pintype "power_in"))
    )
    (net (code "38") (name "Net-(24V_POWER-Pad1)") (class "Default")
      (node (ref "24V_POWER") (pin "1") (pinfunction "1_1") (pintype "passive"))
      (node (ref "FUSE") (pin "1") (pinfunction "1_1") (pintype "passive"))
    )
    (net (code "39") (name "Net-(D8-PadC)") (class "Default")
      (node (ref "D8") (pin "C") (pinfunction "C_C") (pintype "passive"))
      (node (ref "R5") (pin "1") (pinfunction "1_1") (pintype "passive"))
    )
    (net (code "40") (name "Net-(IC2-A)") (class "Default")
      (node (ref "IC2") (pin "1") (pinfunction "A_1") (pintype "passive"))
      (node (ref "R7") (pin "2") (pinfunction "2_2") (pintype "passive"))
    )
    (net (code "41") (name "Net-(IC3-A)") (class "Default")
      (node (ref "IC3") (pin "1") (pinfunction "A_1") (pintype "passive"))
      (node (ref "R8") (pin "2") (pinfunction "2_2") (pintype "passive"))
    )
    (net (code "42") (name "unconnected-(5V_POWER-D+-Pad3)") (class "Default")
      (node (ref "5V_POWER") (pin "3") (pinfunction "D+_3") (pintype "bidirectional"))
    )
    (net (code "43") (name "unconnected-(5V_POWER-D--Pad2)") (class "Default")
      (node (ref "5V_POWER") (pin "2") (pinfunction "D-_2") (pintype "bidirectional"))
    )
    (net (code "44") (name "unconnected-(5V_POWER-ID-Pad4)") (class "Default")
      (node (ref "5V_POWER") (pin "4") (pinfunction "ID_4") (pintype "bidirectional"))
    )
    (net (code "45") (name "unconnected-(IC2-B-Pad6)") (class "Default")
      (node (ref "IC2") (pin "6") (pinfunction "B_6") (pintype "passive"))
    )
    (net (code "46") (name "unconnected-(IC2-NC-Pad3)") (class "Default")
      (node (ref "IC2") (pin "3") (pinfunction "NC_3") (pintype "no_connect"))
    )
    (net (code "47") (name "unconnected-(IC3-B-Pad6)") (class "Default")
      (node (ref "IC3") (pin "6") (pinfunction "B_6") (pintype "passive"))
    )
    (net (code "48") (name "unconnected-(IC3-NC-Pad3)") (class "Default")
      (node (ref "IC3") (pin "3") (pinfunction "NC_3") (pintype "no_connect"))
    )
    (net (code "49") (name "unconnected-(ST-LINK_V2-Pad11)") (class "Default")
      (node (ref "ST-LINK_V2") (pin "11") (pinfunction "11_11") (pintype "bidirectional"))
    )
    (net (code "50") (name "unconnected-(ST-LINK_V2-Pad17)") (class "Default")
      (node (ref "ST-LINK_V2") (pin "17") (pinfunction "17_17") (pintype "bidirectional"))
    )
    (net (code "51") (name "unconnected-(STM32-Pad49)") (class "Default")
      (node (ref "STM32") (pin "49") (pinfunction "49_49") (pintype "passive"))
    )
    (net (code "52") (name "unconnected-(STM32A-AT0-Pad26)") (class "Default")
      (node (ref "STM32") (pin "26") (pinfunction "AT0_26") (pintype "bidirectional"))
    )
    (net (code "53") (name "unconnected-(STM32A-AT1-Pad27)") (class "Default")
      (node (ref "STM32") (pin "27") (pinfunction "AT1_27") (pintype "bidirectional"))
    )
    (net (code "54") (name "unconnected-(STM32A-OSC_IN-Pad25)") (class "Default")
      (node (ref "STM32") (pin "25") (pinfunction "OSC_IN_25") (pintype "passive"))
    )
    (net (code "55") (name "unconnected-(STM32A-OSC_OUT-Pad24)") (class "Default")
      (node (ref "STM32") (pin "24") (pinfunction "OSC_OUT_24") (pintype "output"))
    )
    (net (code "56") (name "unconnected-(STM32A-PC14-OSC32_IN-Pad2)") (class "Default")
      (node (ref "STM32") (pin "2") (pinfunction "PC14-OSC32_IN_2") (pintype "bidirectional"))
    )
    (net (code "57") (name "unconnected-(STM32A-PC15-OSC32_OUT-Pad3)") (class "Default")
      (node (ref "STM32") (pin "3") (pinfunction "PC15-OSC32_OUT_3") (pintype "output"))
    )
    (net (code "58") (name "unconnected-(STM32A-PE4-Pad30)") (class "Default")
      (node (ref "STM32") (pin "30") (pinfunction "PE4_30") (pintype "passive"))
    )
    (net (code "59") (name "unconnected-(STM32A-PH3-BOOT0-Pad4)") (class "Default")
      (node (ref "STM32") (pin "4") (pinfunction "PH3-BOOT0_4") (pintype "passive"))
    )
    (net (code "60") (name "unconnected-(STM32A-RF1-Pad21)") (class "Default")
      (node (ref "STM32") (pin "21") (pinfunction "RF1_21") (pintype "passive"))
    )
    (net (code "61") (name "unconnected-(STM32A-VBAT-Pad1)") (class "Default")
      (node (ref "STM32") (pin "1") (pinfunction "VBAT_1") (pintype "passive"))
    )
    (net (code "62") (name "unconnected-(UART-ID-Pad4)") (class "Default")
      (node (ref "UART") (pin "4") (pinfunction "ID_4") (pintype "bidirectional"))
    )
  )
)
